# Esquematico.net
KiCad netlist of a schematic drawn in Altium Designer
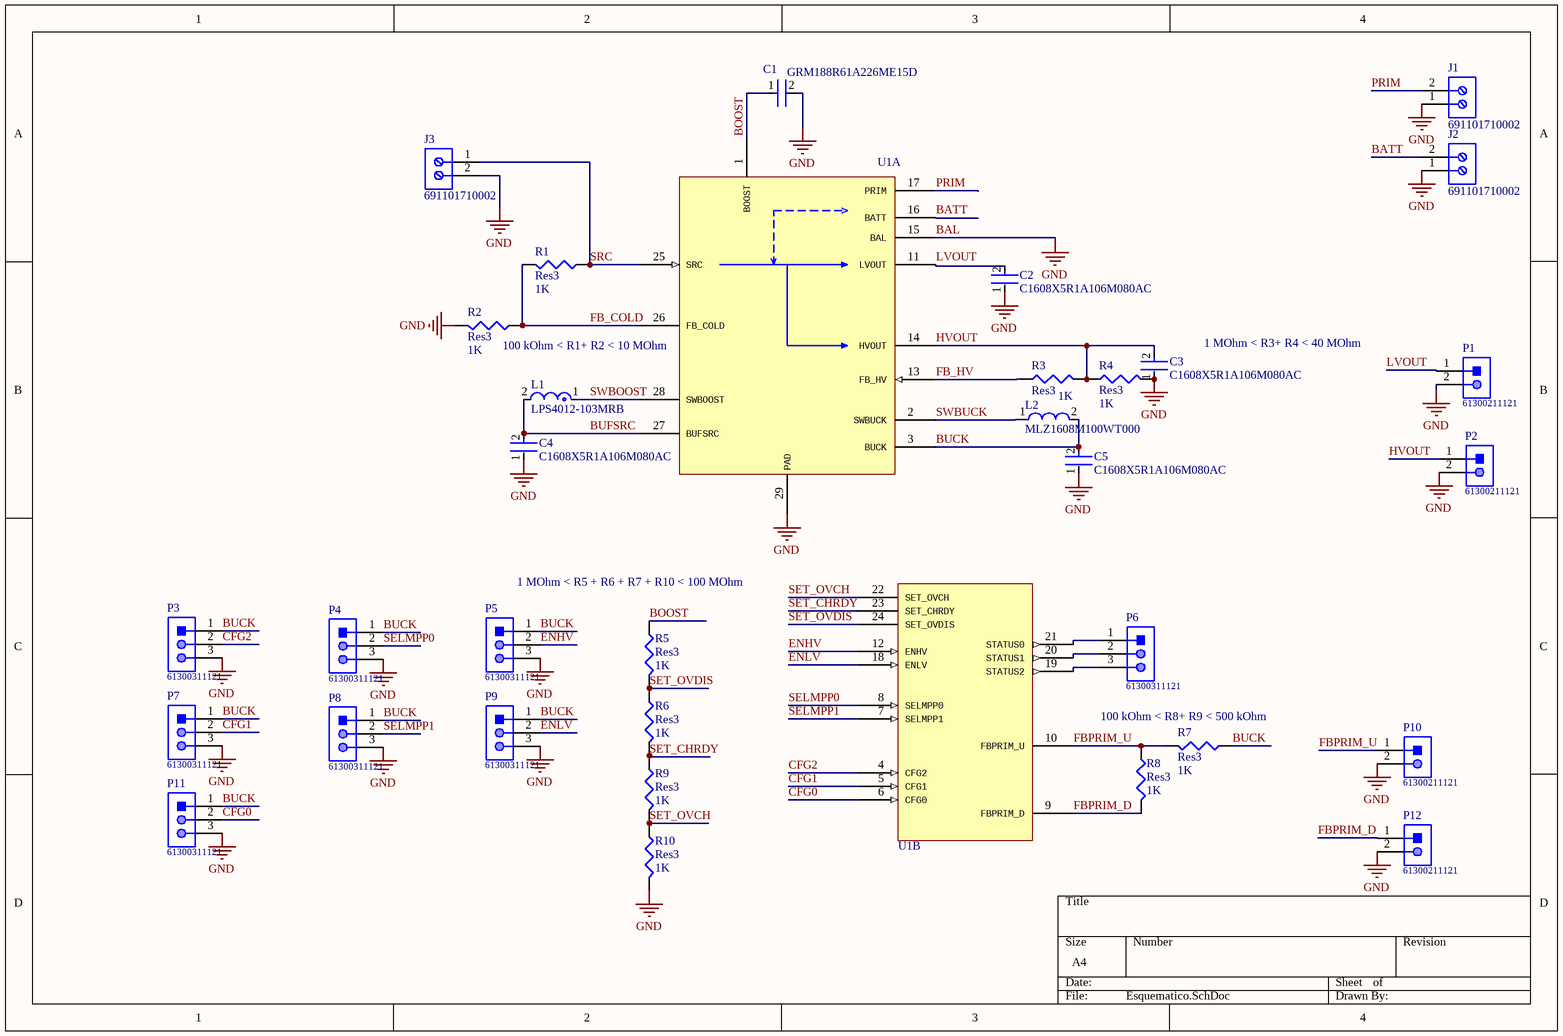
[diagram p0: Esquematico.SchDoc]

(export (version "E")
  (design (tool "Eeschema 10.0.6"))
  (components
    (comp (ref "C1")
      (value "GRM188R61A226ME15D")
      (footprint "FP-GRM188-0_2-IPC_C")
      (description "Chip Multilayer Ceramic Capacitors for General Purpose, 0603, 22uF, X5R, 15%, 20%, 10V")
      (fields (field (name "TOLERANCE") "20%"))
      (libsource (lib "Altium Content Vault") (part "11868f565c42a9108669ba33697ecf6"))
    )
    (comp (ref "C2")
      (value "C1608X5R1A106M080AC")
      (footprint "FP-C1608-080-0_1-IPC_A")
      (description "Multilayer Ceramic Capacitors 10μF ±20% 10V X5R SMD 0603")
      (fields (field (name "TOLERANCE") "20%"))
      (libsource (lib "Altium Content Vault") (part "236180d848d6139a670b325ea6854c9"))
    )
    (comp (ref "C3")
      (value "C1608X5R1A106M080AC")
      (footprint "FP-C1608-080-0_1-IPC_A")
      (description "Multilayer Ceramic Capacitors 10μF ±20% 10V X5R SMD 0603")
      (fields (field (name "TOLERANCE") "20%"))
      (libsource (lib "Altium Content Vault") (part "236180d848d6139a670b325ea6854c9"))
    )
    (comp (ref "C4")
      (value "C1608X5R1A106M080AC")
      (footprint "FP-C1608-080-0_1-IPC_A")
      (description "Multilayer Ceramic Capacitors 10μF ±20% 10V X5R SMD 0603")
      (fields (field (name "TOLERANCE") "20%"))
      (libsource (lib "Altium Content Vault") (part "236180d848d6139a670b325ea6854c9"))
    )
    (comp (ref "C5")
      (value "C1608X5R1A106M080AC")
      (footprint "FP-C1608-080-0_1-IPC_A")
      (description "Multilayer Ceramic Capacitors 10μF ±20% 10V X5R SMD 0603")
      (fields (field (name "TOLERANCE") "20%"))
      (libsource (lib "Altium Content Vault") (part "236180d848d6139a670b325ea6854c9"))
    )
    (comp (ref "J1")
      (value "691101710002")
      (footprint "691101710002")
      (description "Series 101 - 5.00 mm Horizontal Entry Modular with Pressure Clamp WR-TBL, 2 pin")
      (fields (field (name "MANUFACTURER") "Wurth Elektronik") (field (name "PUBLISHER") "WurthElektronik"))
      (libsource (lib "") (part "WE-CN-1P-F-TB2_1"))
    )
    (comp (ref "J2")
      (value "691101710002")
      (footprint "691101710002")
      (description "Series 101 - 5.00 mm Horizontal Entry Modular with Pressure Clamp WR-TBL, 2 pin")
      (fields (field (name "MANUFACTURER") "Wurth Elektronik") (field (name "PUBLISHER") "WurthElektronik"))
      (libsource (lib "Altium Content Vault") (part "WE-CN-1P-F-TB2"))
    )
    (comp (ref "J3")
      (value "691101710002")
      (footprint "691101710002")
      (description "Series 101 - 5.00 mm Horizontal Entry Modular with Pressure Clamp WR-TBL, 2 pin")
      (fields (field (name "MANUFACTURER") "Wurth Elektronik") (field (name "PUBLISHER") "WurthElektronik"))
      (libsource (lib "") (part "WE-CN-1P-F-TB2_1"))
    )
    (comp (ref "L1")
      (value "LPS4012-103MRB")
      (footprint "FP-LPS4012-MFG")
      (description "Power Inductor (SMD), 10 µH, 550 mA, Shielded, 1 A, LPS4012 Series, 3.9mm x 3.9mm x 1.1mm")
      (fields (field (name "TOLERANCE") "20%"))
      (libsource (lib "Altium Content Vault") (part "4cc4b267dca4c8e51f7102f422741d8"))
    )
    (comp (ref "L2")
      (value "MLZ1608M100WT000")
      (footprint "FP-MLZ1608-IPC_C")
      (description "Shielded Multilayer Inductor 10uH ±20% 250mA 1365mΩ SMD 0603")
      (fields (field (name "TOLERANCE") "20%"))
      (libsource (lib "Altium Content Vault") (part "725321dda6339637d4d059423bc1c3c"))
    )
    (comp (ref "P1")
      (value "61300211121")
      (footprint "61300211121")
      (description "THT Vertical Pin Header WR-PHD, Pitch 2.54 mm, Single Row, 2 pins")
      (fields (field (name "MANUFACTURER") "Wurth Elektronik") (field (name "PUBLISHER") "WurthElektronik"))
      (libsource (lib "Altium Content Vault") (part "WE-CN-1P-M-R2"))
    )
    (comp (ref "P2")
      (value "61300211121")
      (footprint "61300211121")
      (description "THT Vertical Pin Header WR-PHD, Pitch 2.54 mm, Single Row, 2 pins")
      (fields (field (name "MANUFACTURER") "Wurth Elektronik") (field (name "PUBLISHER") "WurthElektronik"))
      (libsource (lib "Altium Content Vault") (part "WE-CN-1P-M-R2"))
    )
    (comp (ref "P3")
      (value "61300311121")
      (footprint "61300311121")
      (description "THT Vertical Pin Header WR-PHD, Pitch 2.54 mm, Single Row, 3 pins")
      (fields (field (name "MANUFACTURER") "Wurth Elektronik") (field (name "PUBLISHER") "WurthElektronik"))
      (libsource (lib "Altium Content Vault") (part "WE-CN-1P-M-R3"))
    )
    (comp (ref "P4")
      (value "61300311121")
      (footprint "61300311121")
      (description "THT Vertical Pin Header WR-PHD, Pitch 2.54 mm, Single Row, 3 pins")
      (fields (field (name "MANUFACTURER") "Wurth Elektronik") (field (name "PUBLISHER") "WurthElektronik"))
      (libsource (lib "Altium Content Vault") (part "WE-CN-1P-M-R3"))
    )
    (comp (ref "P5")
      (value "61300311121")
      (footprint "61300311121")
      (description "THT Vertical Pin Header WR-PHD, Pitch 2.54 mm, Single Row, 3 pins")
      (fields (field (name "MANUFACTURER") "Wurth Elektronik") (field (name "PUBLISHER") "WurthElektronik"))
      (libsource (lib "Altium Content Vault") (part "WE-CN-1P-M-R3"))
    )
    (comp (ref "P6")
      (value "61300311121")
      (footprint "61300311121")
      (description "THT Vertical Pin Header WR-PHD, Pitch 2.54 mm, Single Row, 3 pins")
      (fields (field (name "MANUFACTURER") "Wurth Elektronik") (field (name "PUBLISHER") "WurthElektronik"))
      (libsource (lib "") (part "WE-CN-1P-M-R3_1"))
    )
    (comp (ref "P7")
      (value "61300311121")
      (footprint "61300311121")
      (description "THT Vertical Pin Header WR-PHD, Pitch 2.54 mm, Single Row, 3 pins")
      (fields (field (name "MANUFACTURER") "Wurth Elektronik") (field (name "PUBLISHER") "WurthElektronik"))
      (libsource (lib "Altium Content Vault") (part "WE-CN-1P-M-R3"))
    )
    (comp (ref "P8")
      (value "61300311121")
      (footprint "61300311121")
      (description "THT Vertical Pin Header WR-PHD, Pitch 2.54 mm, Single Row, 3 pins")
      (fields (field (name "MANUFACTURER") "Wurth Elektronik") (field (name "PUBLISHER") "WurthElektronik"))
      (libsource (lib "Altium Content Vault") (part "WE-CN-1P-M-R3"))
    )
    (comp (ref "P9")
      (value "61300311121")
      (footprint "61300311121")
      (description "THT Vertical Pin Header WR-PHD, Pitch 2.54 mm, Single Row, 3 pins")
      (fields (field (name "MANUFACTURER") "Wurth Elektronik") (field (name "PUBLISHER") "WurthElektronik"))
      (libsource (lib "Altium Content Vault") (part "WE-CN-1P-M-R3"))
    )
    (comp (ref "P10")
      (value "61300211121")
      (footprint "61300211121")
      (description "THT Vertical Pin Header WR-PHD, Pitch 2.54 mm, Single Row, 2 pins")
      (fields (field (name "MANUFACTURER") "Wurth Elektronik") (field (name "PUBLISHER") "WurthElektronik"))
      (libsource (lib "Altium Content Vault") (part "WE-CN-1P-M-R2"))
    )
    (comp (ref "P11")
      (value "61300311121")
      (footprint "61300311121")
      (description "THT Vertical Pin Header WR-PHD, Pitch 2.54 mm, Single Row, 3 pins")
      (fields (field (name "MANUFACTURER") "Wurth Elektronik") (field (name "PUBLISHER") "WurthElektronik"))
      (libsource (lib "Altium Content Vault") (part "WE-CN-1P-M-R3"))
    )
    (comp (ref "P12")
      (value "61300211121")
      (footprint "61300211121")
      (description "THT Vertical Pin Header WR-PHD, Pitch 2.54 mm, Single Row, 2 pins")
      (fields (field (name "MANUFACTURER") "Wurth Elektronik") (field (name "PUBLISHER") "WurthElektronik"))
      (libsource (lib "Altium Content Vault") (part "WE-CN-1P-M-R2"))
    )
    (comp (ref "R1")
      (value "Res3")
      (footprint "J1-0603")
      (description "Resistor")
      (fields (field (name "ALTIUM_VALUE") "1K") (field (name "PUBLISHER") "Altium Limited"))
      (libsource (lib "Miscellaneous Devices") (part "Res3"))
    )
    (comp (ref "R2")
      (value "Res3")
      (footprint "J1-0603")
      (description "Resistor")
      (fields (field (name "ALTIUM_VALUE") "1K") (field (name "PUBLISHER") "Altium Limited"))
      (libsource (lib "Miscellaneous Devices") (part "Res3"))
    )
    (comp (ref "R3")
      (value "Res3")
      (footprint "J1-0603")
      (description "Resistor")
      (fields (field (name "ALTIUM_VALUE") "1K") (field (name "PUBLISHER") "Altium Limited"))
      (libsource (lib "Miscellaneous Devices") (part "Res3"))
    )
    (comp (ref "R4")
      (value "Res3")
      (footprint "J1-0603")
      (description "Resistor")
      (fields (field (name "ALTIUM_VALUE") "1K") (field (name "PUBLISHER") "Altium Limited"))
      (libsource (lib "Miscellaneous Devices") (part "Res3"))
    )
    (comp (ref "R5")
      (value "Res3")
      (footprint "J1-0603")
      (description "Resistor")
      (fields (field (name "ALTIUM_VALUE") "1K") (field (name "PUBLISHER") "Altium Limited"))
      (libsource (lib "Miscellaneous Devices") (part "Res3"))
    )
    (comp (ref "R6")
      (value "Res3")
      (footprint "J1-0603")
      (description "Resistor")
      (fields (field (name "ALTIUM_VALUE") "1K") (field (name "PUBLISHER") "Altium Limited"))
      (libsource (lib "Miscellaneous Devices") (part "Res3"))
    )
    (comp (ref "R7")
      (value "Res3")
      (footprint "J1-0603")
      (description "Resistor")
      (fields (field (name "ALTIUM_VALUE") "1K") (field (name "PUBLISHER") "Altium Limited"))
      (libsource (lib "Miscellaneous Devices") (part "Res3"))
    )
    (comp (ref "R8")
      (value "Res3")
      (footprint "J1-0603")
      (description "Resistor")
      (fields (field (name "ALTIUM_VALUE") "1K") (field (name "PUBLISHER") "Altium Limited"))
      (libsource (lib "Miscellaneous Devices") (part "Res3"))
    )
    (comp (ref "R9")
      (value "Res3")
      (footprint "J1-0603")
      (description "Resistor")
      (fields (field (name "ALTIUM_VALUE") "1K") (field (name "PUBLISHER") "Altium Limited"))
      (libsource (lib "Miscellaneous Devices") (part "Res3"))
    )
    (comp (ref "R10")
      (value "Res3")
      (footprint "J1-0603")
      (description "Resistor")
      (fields (field (name "ALTIUM_VALUE") "1K") (field (name "PUBLISHER") "Altium Limited"))
      (libsource (lib "Miscellaneous Devices") (part "Res3"))
    )
    (comp (ref "U1")
      (value "AEM10941 - Symbol QFN28")
      (footprint "QFN28 5x5mm Pitch=0.5mm ThPad=3.15x3.15mm")
      (libsource (lib "AEM10941") (part "AEM10941 - Symbol QFN28"))
    )
  )
  (nets
    (net (code "1") (name "/BATT") (class "Default")
      (node (ref "J2") (pin "2") (pinfunction "2_2") (pintype "passive"))
      (node (ref "U1") (pin "16") (pinfunction "BATT_16") (pintype "passive"))
    )
    (net (code "2") (name "/BOOST") (class "Default")
      (node (ref "C1") (pin "1") (pinfunction "1_1") (pintype "passive"))
      (node (ref "R5") (pin "1") (pinfunction "1_1") (pintype "passive"))
      (node (ref "U1") (pin "1") (pinfunction "BOOST_1") (pintype "passive"))
    )
    (net (code "3") (name "/BUCK") (class "Default")
      (node (ref "C5") (pin "2") (pinfunction "2_2") (pintype "passive"))
      (node (ref "L2") (pin "2") (pinfunction "2_2") (pintype "passive"))
      (node (ref "P11") (pin "1") (pinfunction "1_1") (pintype "passive"))
      (node (ref "P3") (pin "1") (pinfunction "1_1") (pintype "passive"))
      (node (ref "P4") (pin "1") (pinfunction "1_1") (pintype "passive"))
      (node (ref "P5") (pin "1") (pinfunction "1_1") (pintype "passive"))
      (node (ref "P7") (pin "1") (pinfunction "1_1") (pintype "passive"))
      (node (ref "P8") (pin "1") (pinfunction "1_1") (pintype "passive"))
      (node (ref "P9") (pin "1") (pinfunction "1_1") (pintype "passive"))
      (node (ref "R7") (pin "1") (pinfunction "1_1") (pintype "passive"))
      (node (ref "U1") (pin "3") (pinfunction "BUCK_3") (pintype "passive"))
    )
    (net (code "4") (name "/BUFSRC") (class "Default")
      (node (ref "C4") (pin "2") (pinfunction "2_2") (pintype "passive"))
      (node (ref "L1") (pin "2") (pinfunction "2_2") (pintype "passive"))
      (node (ref "U1") (pin "27") (pinfunction "BUFSRC_27") (pintype "passive"))
    )
    (net (code "5") (name "/CFG0") (class "Default")
      (node (ref "P11") (pin "2") (pinfunction "2_2") (pintype "passive"))
      (node (ref "U1") (pin "6") (pinfunction "CFG0_6") (pintype "input"))
    )
    (net (code "6") (name "/CFG1") (class "Default")
      (node (ref "P7") (pin "2") (pinfunction "2_2") (pintype "passive"))
      (node (ref "U1") (pin "5") (pinfunction "CFG1_5") (pintype "input"))
    )
    (net (code "7") (name "/CFG2") (class "Default")
      (node (ref "P3") (pin "2") (pinfunction "2_2") (pintype "passive"))
      (node (ref "U1") (pin "4") (pinfunction "CFG2_4") (pintype "input"))
    )
    (net (code "8") (name "/ENHV") (class "Default")
      (node (ref "P5") (pin "2") (pinfunction "2_2") (pintype "passive"))
      (node (ref "U1") (pin "12") (pinfunction "ENHV_12") (pintype "input"))
    )
    (net (code "9") (name "/ENLV") (class "Default")
      (node (ref "P9") (pin "2") (pinfunction "2_2") (pintype "passive"))
      (node (ref "U1") (pin "18") (pinfunction "ENLV_18") (pintype "input"))
    )
    (net (code "10") (name "/FBPRIM_D") (class "Default")
      (node (ref "P12") (pin "1") (pinfunction "1_1") (pintype "passive"))
      (node (ref "R8") (pin "2") (pinfunction "2_2") (pintype "passive"))
      (node (ref "U1") (pin "9") (pinfunction "FBPRIM_D_9") (pintype "passive"))
    )
    (net (code "11") (name "/FBPRIM_U") (class "Default")
      (node (ref "P10") (pin "1") (pinfunction "1_1") (pintype "passive"))
      (node (ref "R7") (pin "2") (pinfunction "2_2") (pintype "passive"))
      (node (ref "R8") (pin "1") (pinfunction "1_1") (pintype "passive"))
      (node (ref "U1") (pin "10") (pinfunction "FBPRIM_U_10") (pintype "passive"))
    )
    (net (code "12") (name "/FB_COLD") (class "Default")
      (node (ref "R1") (pin "2") (pinfunction "2_2") (pintype "passive"))
      (node (ref "R2") (pin "1") (pinfunction "1_1") (pintype "passive"))
      (node (ref "U1") (pin "26") (pinfunction "FB_COLD_26") (pintype "passive"))
    )
    (net (code "13") (name "/FB_HV") (class "Default")
      (node (ref "R3") (pin "1") (pinfunction "1_1") (pintype "passive"))
      (node (ref "U1") (pin "13") (pinfunction "FB_HV_13") (pintype "input"))
    )
    (net (code "14") (name "/HVOUT") (class "Default")
      (node (ref "C3") (pin "2") (pinfunction "2_2") (pintype "passive"))
      (node (ref "P2") (pin "1") (pinfunction "1_1") (pintype "passive"))
      (node (ref "R3") (pin "2") (pinfunction "2_2") (pintype "passive"))
      (node (ref "R4") (pin "1") (pinfunction "1_1") (pintype "passive"))
      (node (ref "U1") (pin "14") (pinfunction "HVOUT_14") (pintype "power_in"))
    )
    (net (code "15") (name "/LVOUT") (class "Default")
      (node (ref "C2") (pin "2") (pinfunction "2_2") (pintype "passive"))
      (node (ref "P1") (pin "1") (pinfunction "1_1") (pintype "passive"))
      (node (ref "U1") (pin "11") (pinfunction "LVOUT_11") (pintype "power_in"))
    )
    (net (code "16") (name "/PRIM") (class "Default")
      (node (ref "J1") (pin "2") (pinfunction "2_2") (pintype "passive"))
      (node (ref "U1") (pin "17") (pinfunction "PRIM_17") (pintype "passive"))
    )
    (net (code "17") (name "/SELMPP0") (class "Default")
      (node (ref "P4") (pin "2") (pinfunction "2_2") (pintype "passive"))
      (node (ref "U1") (pin "8") (pinfunction "SELMPP0_8") (pintype "input"))
    )
    (net (code "18") (name "/SELMPP1") (class "Default")
      (node (ref "P8") (pin "2") (pinfunction "2_2") (pintype "passive"))
      (node (ref "U1") (pin "7") (pinfunction "SELMPP1_7") (pintype "input"))
    )
    (net (code "19") (name "/SET_CHRDY") (class "Default")
      (node (ref "R6") (pin "2") (pinfunction "2_2") (pintype "passive"))
      (node (ref "R9") (pin "1") (pinfunction "1_1") (pintype "passive"))
      (node (ref "U1") (pin "23") (pinfunction "SET_CHRDY_23") (pintype "passive"))
    )
    (net (code "20") (name "/SET_OVCH") (class "Default")
      (node (ref "R10") (pin "1") (pinfunction "1_1") (pintype "passive"))
      (node (ref "R9") (pin "2") (pinfunction "2_2") (pintype "passive"))
      (node (ref "U1") (pin "22") (pinfunction "SET_OVCH_22") (pintype "passive"))
    )
    (net (code "21") (name "/SET_OVDIS") (class "Default")
      (node (ref "R5") (pin "2") (pinfunction "2_2") (pintype "passive"))
      (node (ref "R6") (pin "1") (pinfunction "1_1") (pintype "passive"))
      (node (ref "U1") (pin "24") (pinfunction "SET_OVDIS_24") (pintype "passive"))
    )
    (net (code "22") (name "/SRC") (class "Default")
      (node (ref "J3") (pin "1") (pinfunction "1_1") (pintype "passive"))
      (node (ref "R1") (pin "1") (pinfunction "1_1") (pintype "passive"))
      (node (ref "U1") (pin "25") (pinfunction "SRC_25") (pintype "input"))
    )
    (net (code "23") (name "/SWBOOST") (class "Default")
      (node (ref "L1") (pin "1") (pinfunction "1_1") (pintype "passive"))
      (node (ref "U1") (pin "28") (pinfunction "SWBOOST_28") (pintype "passive"))
    )
    (net (code "24") (name "/SWBUCK") (class "Default")
      (node (ref "L2") (pin "1") (pinfunction "1_1") (pintype "passive"))
      (node (ref "U1") (pin "2") (pinfunction "SWBUCK_2") (pintype "passive"))
    )
    (net (code "25") (name "GND") (class "Default")
      (node (ref "C1") (pin "2") (pinfunction "2_2") (pintype "passive"))
      (node (ref "C2") (pin "1") (pinfunction "1_1") (pintype "passive"))
      (node (ref "C3") (pin "1") (pinfunction "1_1") (pintype "passive"))
      (node (ref "C4") (pin "1") (pinfunction "1_1") (pintype "passive"))
      (node (ref "C5") (pin "1") (pinfunction "1_1") (pintype "passive"))
      (node (ref "J1") (pin "1") (pinfunction "1_1") (pintype "passive"))
      (node (ref "J2") (pin "1") (pinfunction "1_1") (pintype "passive"))
      (node (ref "J3") (pin "2") (pinfunction "2_2") (pintype "passive"))
      (node (ref "P1") (pin "2") (pinfunction "2_2") (pintype "passive"))
      (node (ref "P10") (pin "2") (pinfunction "2_2") (pintype "passive"))
      (node (ref "P11") (pin "3") (pinfunction "3_3") (pintype "passive"))
      (node (ref "P12") (pin "2") (pinfunction "2_2") (pintype "passive"))
      (node (ref "P2") (pin "2") (pinfunction "2_2") (pintype "passive"))
      (node (ref "P3") (pin "3") (pinfunction "3_3") (pintype "passive"))
      (node (ref "P4") (pin "3") (pinfunction "3_3") (pintype "passive"))
      (node (ref "P5") (pin "3") (pinfunction "3_3") (pintype "passive"))
      (node (ref "P7") (pin "3") (pinfunction "3_3") (pintype "passive"))
      (node (ref "P8") (pin "3") (pinfunction "3_3") (pintype "passive"))
      (node (ref "P9") (pin "3") (pinfunction "3_3") (pintype "passive"))
      (node (ref "R10") (pin "2") (pinfunction "2_2") (pintype "passive"))
      (node (ref "R2") (pin "2") (pinfunction "2_2") (pintype "passive"))
      (node (ref "R4") (pin "2") (pinfunction "2_2") (pintype "passive"))
      (node (ref "U1") (pin "15") (pinfunction "BAL_15") (pintype "passive"))
      (node (ref "U1") (pin "29") (pinfunction "PAD_29") (pintype "power_in"))
    )
    (net (code "26") (name "Net-(U1B-STATUS0)") (class "Default")
      (node (ref "P6") (pin "1") (pinfunction "1_1") (pintype "passive"))
      (node (ref "U1") (pin "21") (pinfunction "STATUS0_21") (pintype "output"))
    )
    (net (code "27") (name "Net-(U1B-STATUS1)") (class "Default")
      (node (ref "P6") (pin "2") (pinfunction "2_2") (pintype "passive"))
      (node (ref "U1") (pin "20") (pinfunction "STATUS1_20") (pintype "output"))
    )
    (net (code "28") (name "Net-(U1B-STATUS2)") (class "Default")
      (node (ref "P6") (pin "3") (pinfunction "3_3") (pintype "passive"))
      (node (ref "U1") (pin "19") (pinfunction "STATUS2_19") (pintype "output"))
    )
  )
)
